# Main.net
KiCad netlist of a schematic drawn in Altium Designer
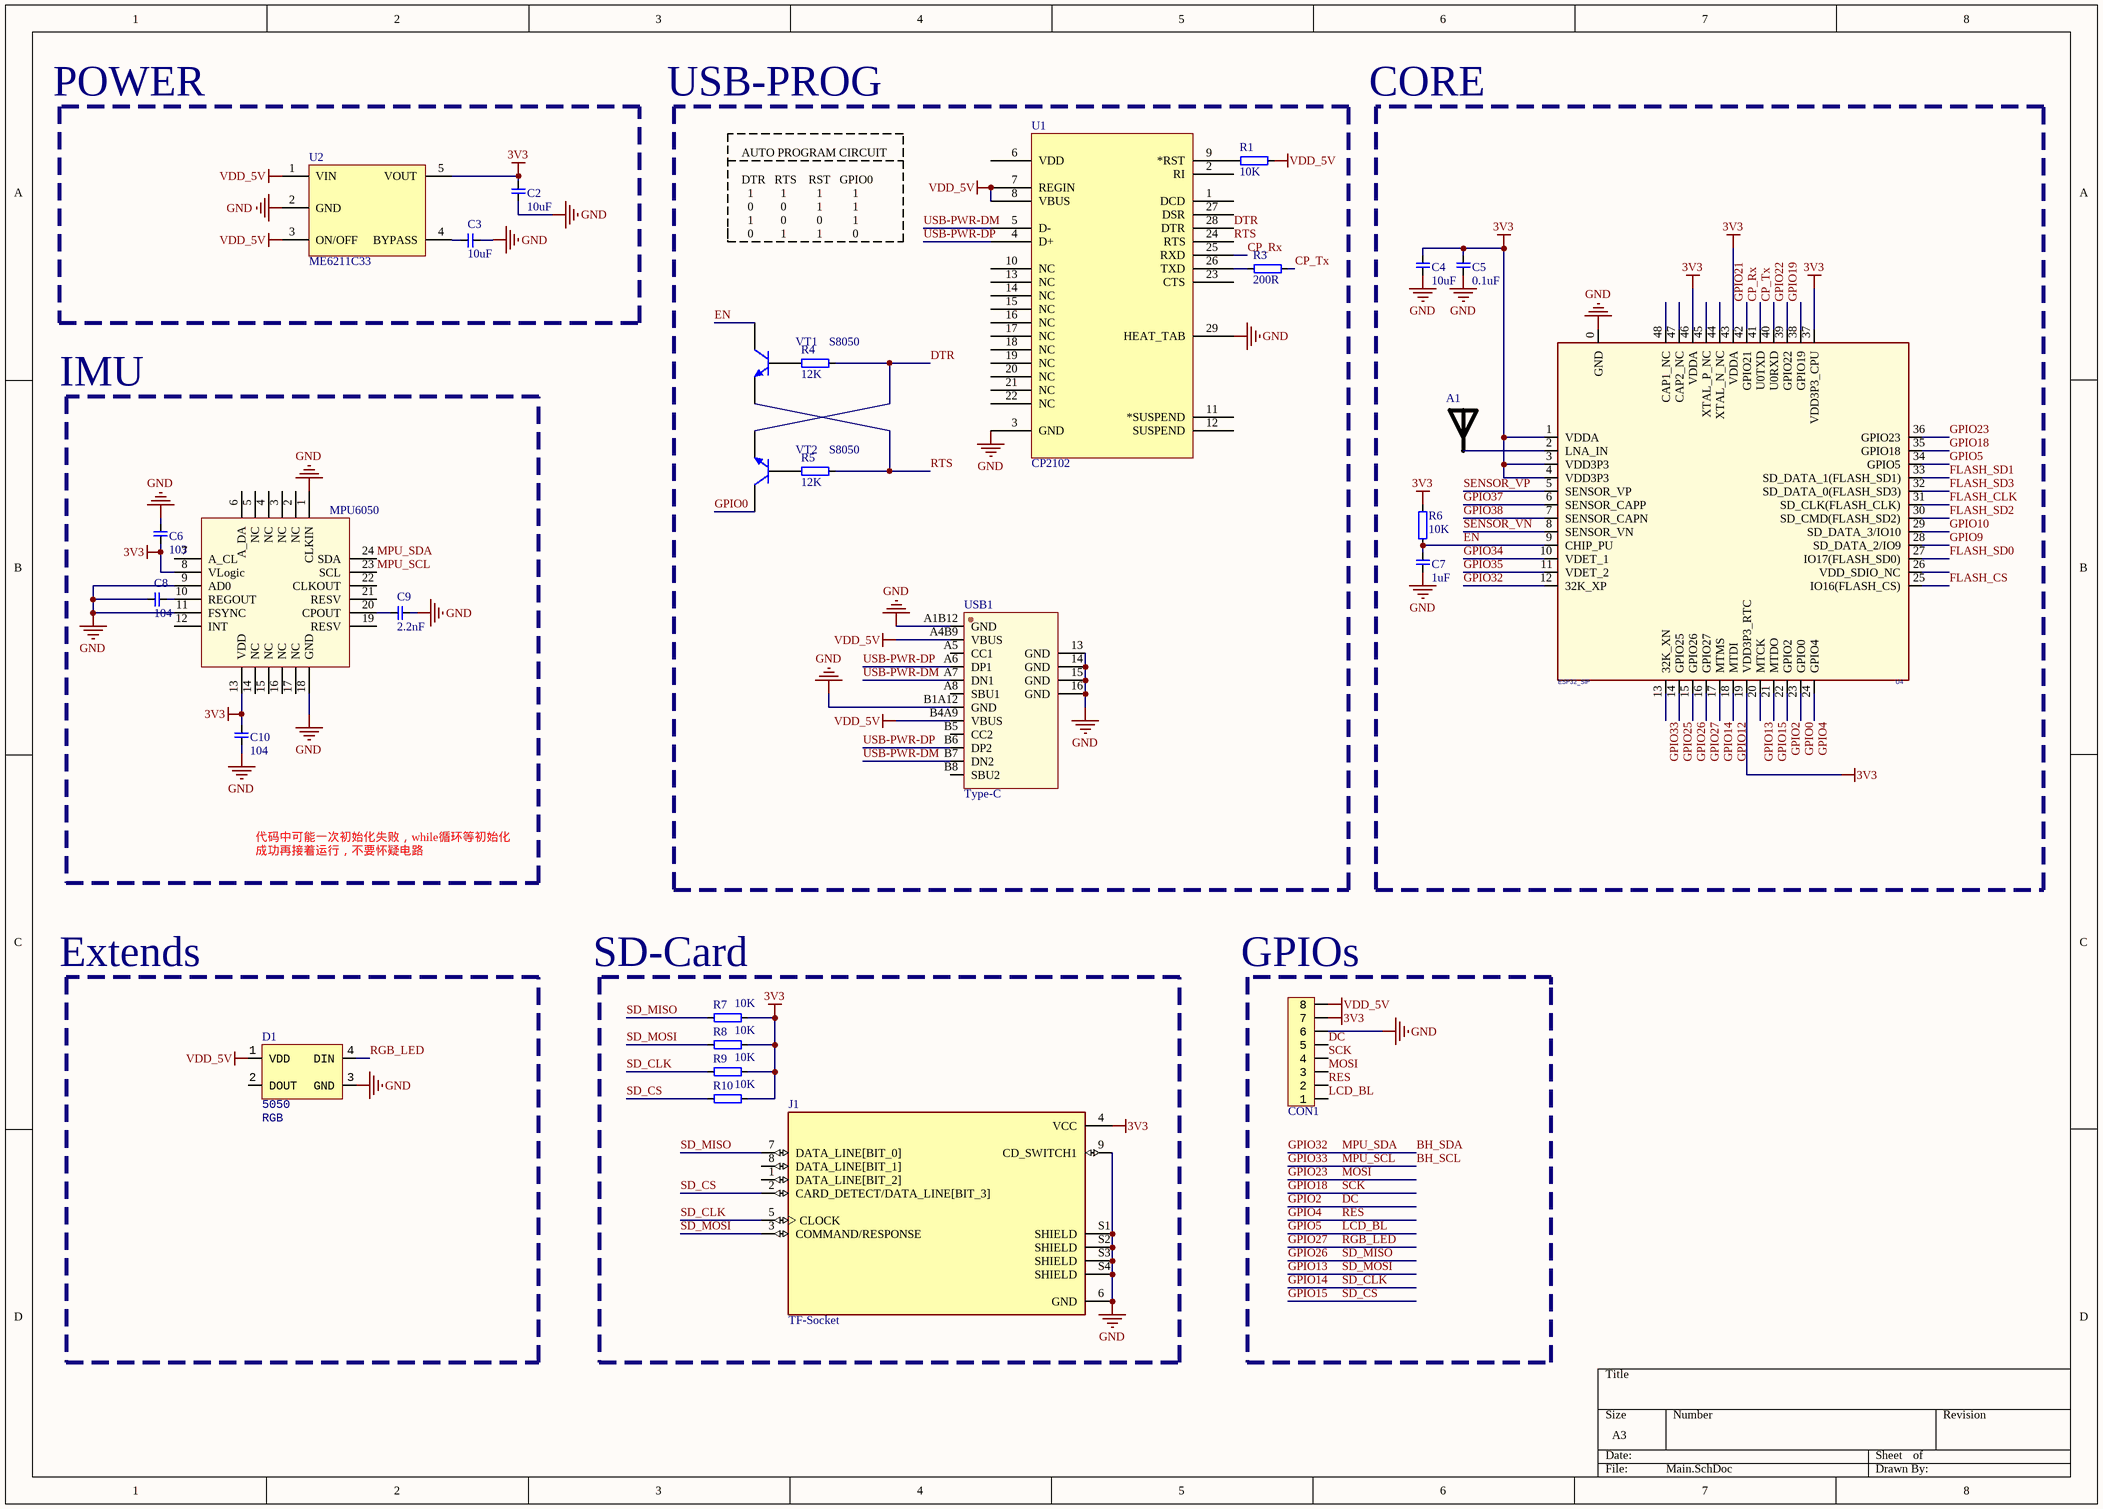
[diagram p0: Main.SchDoc]

(export (version "E")
  (design (tool "Eeschema 10.0.6"))
  (components
    (comp (ref "A1")
      (value "RAINSUN")
      (footprint "ANT-Rainsun-AN5120")
      (libsource (lib "MyPcbLib") (part "ANT-Rainsun-AP5120"))
    )
    (comp (ref "C2") (value "10uF") (footprint "CAP_0603") (libsource (lib "基本元件库") (part "cap")))
    (comp (ref "C3") (value "10uF") (footprint "CAP_0603") (libsource (lib "基本元件库") (part "cap")))
    (comp (ref "C4") (value "10uF") (footprint "CAP_0603") (libsource (lib "基本元件库") (part "cap")))
    (comp (ref "C5") (value "0.1uF") (footprint "CAP_0603") (libsource (lib "基本元件库") (part "cap")))
    (comp (ref "C6") (value "103") (footprint "CAP_0603") (libsource (lib "基本元件库") (part "cap")))
    (comp (ref "C7") (value "1uF") (footprint "CAP_0603") (libsource (lib "基本元件库") (part "cap")))
    (comp (ref "C8") (value "104") (footprint "CAP_0603") (libsource (lib "基本元件库") (part "cap")))
    (comp (ref "C9") (value "2.2nF") (footprint "CAP_0603") (libsource (lib "基本元件库") (part "cap")))
    (comp (ref "C10") (value "104") (footprint "CAP_0603") (libsource (lib "基本元件库") (part "cap")))
    (comp (ref "CON1")
      (value "FFC_0.5_8")
      (footprint "FFC_0.5_8")
      (description "FFC")
      (libsource (lib "KitSprout") (part "FFC_0.5_8"))
    )
    (comp (ref "D1")
      (value "RGB")
      (footprint "LED_5050_WS2812B")
      (description "LED")
      (fields (field (name "TYPE") "5050"))
      (libsource (lib "基本元件库") (part "RGB_4WIC"))
    )
    (comp (ref "J1")
      (value "TF-Socket")
      (footprint "TF-Card-Amphenol with TF - nohole")
      (description "9 _8 + 4_ Position Card Connector Secure Digital - microSDâ„¢ Surface Mount, Right Angle Gold")
      (fields (field (name "MP") "1140084168") (field (name "MF") "Amphenol Commercial Products"))
      (libsource (lib "IC") (part "TF-Socket"))
    )
    (comp (ref "R1") (value "10K") (footprint "RES_0603") (libsource (lib "基本元件库") (part "Res")))
    (comp (ref "R3") (value "200R") (footprint "RES_0603") (libsource (lib "基本元件库") (part "Res")))
    (comp (ref "R4") (value "12K") (footprint "RES_0603") (libsource (lib "基本元件库") (part "Res")))
    (comp (ref "R5") (value "12K") (footprint "RES_0603") (libsource (lib "基本元件库") (part "Res")))
    (comp (ref "R6") (value "10K") (footprint "RES_0603") (libsource (lib "基本元件库") (part "Res")))
    (comp (ref "R7") (value "10K") (footprint "RES_0603") (libsource (lib "基本元件库") (part "Res")))
    (comp (ref "R8") (value "10K") (footprint "RES_0603") (libsource (lib "基本元件库") (part "Res")))
    (comp (ref "R9") (value "10K") (footprint "RES_0603") (libsource (lib "基本元件库") (part "Res")))
    (comp (ref "R10") (value "10K") (footprint "RES_0603") (libsource (lib "基本元件库") (part "Res")))
    (comp (ref "U1")
      (value "CP2102")
      (footprint "QFN-28")
      (description "USB转TTL")
      (libsource (lib "mLib") (part "CP2102"))
    )
    (comp (ref "U2")
      (value "ME6211C33")
      (footprint "SOT23-5")
      (description "LDO")
      (libsource (lib "MyPcbLib") (part "LP2992"))
    )
    (comp (ref "U3")
      (value "MPU6050")
      (footprint "QFN-24")
      (description "六轴传感器")
      (libsource (lib "mLib") (part "MPU6050"))
    )
    (comp (ref "U4")
      (value "ESP32_SIP")
      (footprint "QFN-48_7X7")
      (libsource (lib "MyPcbLib") (part "ESP32-PICO"))
    )
    (comp (ref "USB1")
      (value "Type-C")
      (footprint "TypeC-304-16BCP")
      (libsource (lib "接插件库") (part "Type-C母口"))
    )
    (comp (ref "VT1")
      (value "S8050")
      (footprint "SMT_TRIODE_NPN")
      (description "Surface mount NPN transistor, package SOT-23")
      (libsource (lib "MyPcbLib") (part "SMT_TRIODE_NPN"))
    )
    (comp (ref "VT2")
      (value "S8050")
      (footprint "SMT_TRIODE_NPN")
      (description "Surface mount NPN transistor, package SOT-23")
      (libsource (lib "MyPcbLib") (part "SMT_TRIODE_NPN"))
    )
  )
  (nets
    (net (code "1") (name "/BH_SCL") (class "Default")
      (node (ref "U3") (pin "23") (pinfunction "SCL_23") (pintype "passive"))
      (node (ref "U4") (pin "13") (pinfunction "32K_XN_13") (pintype "passive"))
    )
    (net (code "2") (name "/BH_SDA") (class "Default")
      (node (ref "U3") (pin "24") (pinfunction "SDA_24") (pintype "passive"))
      (node (ref "U4") (pin "12") (pinfunction "32K_XP_12") (pintype "passive"))
    )
    (net (code "3") (name "/CP_Rx") (class "Default")
      (node (ref "U1") (pin "25") (pinfunction "RXD_25") (pintype "passive"))
      (node (ref "U4") (pin "41") (pinfunction "U0TXD_41") (pintype "power_in"))
    )
    (net (code "4") (name "/CP_Tx") (class "Default")
      (node (ref "R3") (pin "1") (pinfunction "1_1") (pintype "passive"))
      (node (ref "U4") (pin "40") (pinfunction "U0RXD_40") (pintype "power_in"))
    )
    (net (code "5") (name "/DC") (class "Default")
      (node (ref "CON1") (pin "5") (pinfunction "5_5") (pintype "passive"))
      (node (ref "U4") (pin "22") (pinfunction "GPIO2_22") (pintype "passive"))
    )
    (net (code "6") (name "/DTR") (class "Default")
      (node (ref "R4") (pin "1") (pinfunction "1_1") (pintype "passive"))
      (node (ref "U1") (pin "28") (pinfunction "DTR_28") (pintype "passive"))
      (node (ref "VT2") (pin "2") (pinfunction "E_2") (pintype "passive"))
    )
    (net (code "7") (name "/EN") (class "Default")
      (node (ref "C7") (pin "2") (pinfunction "2_2") (pintype "passive"))
      (node (ref "R6") (pin "1") (pinfunction "1_1") (pintype "passive"))
      (node (ref "U4") (pin "9") (pinfunction "CHIP_PU_9") (pintype "passive"))
      (node (ref "VT1") (pin "3") (pinfunction "C_3") (pintype "passive"))
    )
    (net (code "8") (name "/FLASH_CLK") (class "Default")
      (node (ref "U4") (pin "31") (pinfunction "SD_CLK(FLASH_CLK)_31") (pintype "passive"))
    )
    (net (code "9") (name "/FLASH_CS") (class "Default")
      (node (ref "U4") (pin "25") (pinfunction "IO16(FLASH_CS)_25") (pintype "passive"))
    )
    (net (code "10") (name "/FLASH_SD0") (class "Default")
      (node (ref "U4") (pin "27") (pinfunction "IO17(FLASH_SD0)_27") (pintype "passive"))
    )
    (net (code "11") (name "/FLASH_SD1") (class "Default")
      (node (ref "U4") (pin "33") (pinfunction "SD_DATA_1(FLASH_SD1)_33") (pintype "passive"))
    )
    (net (code "12") (name "/FLASH_SD2") (class "Default")
      (node (ref "U4") (pin "30") (pinfunction "SD_CMD(FLASH_SD2)_30") (pintype "passive"))
    )
    (net (code "13") (name "/FLASH_SD3") (class "Default")
      (node (ref "U4") (pin "32") (pinfunction "SD_DATA_0(FLASH_SD3)_32") (pintype "passive"))
    )
    (net (code "14") (name "/GPIO0") (class "Default")
      (node (ref "U4") (pin "23") (pinfunction "GPIO0_23") (pintype "passive"))
      (node (ref "VT2") (pin "3") (pinfunction "C_3") (pintype "passive"))
    )
    (net (code "15") (name "/GPIO4") (class "Default")
      (node (ref "CON1") (pin "2") (pinfunction "2_2") (pintype "passive"))
      (node (ref "U4") (pin "24") (pinfunction "GPIO4_24") (pintype "passive"))
    )
    (net (code "16") (name "/GPIO5") (class "Default")
      (node (ref "CON1") (pin "1") (pinfunction "1_1") (pintype "passive"))
      (node (ref "U4") (pin "34") (pinfunction "GPIO5_34") (pintype "passive"))
    )
    (net (code "17") (name "/GPIO9") (class "Default")
      (node (ref "U4") (pin "28") (pinfunction "SD_DATA_2/IO9_28") (pintype "passive"))
    )
    (net (code "18") (name "/GPIO10") (class "Default")
      (node (ref "U4") (pin "29") (pinfunction "SD_DATA_3/IO10_29") (pintype "passive"))
    )
    (net (code "19") (name "/GPIO12") (class "Default")
      (node (ref "U4") (pin "18") (pinfunction "MTDI_18") (pintype "passive"))
    )
    (net (code "20") (name "/GPIO13") (class "Default")
      (node (ref "J1") (pin "3") (pinfunction "COMMAND/RESPONSE_3") (pintype "bidirectional"))
      (node (ref "R8") (pin "2") (pinfunction "2_2") (pintype "passive"))
      (node (ref "U4") (pin "20") (pinfunction "MTCK_20") (pintype "passive"))
    )
    (net (code "21") (name "/GPIO14") (class "Default")
      (node (ref "J1") (pin "5") (pinfunction "CLOCK_5") (pintype "bidirectional"))
      (node (ref "R9") (pin "2") (pinfunction "2_2") (pintype "passive"))
      (node (ref "U4") (pin "17") (pinfunction "MTMS_17") (pintype "passive"))
    )
    (net (code "22") (name "/GPIO15") (class "Default")
      (node (ref "J1") (pin "2") (pinfunction "CARD_DETECT/DATA_LINE[BIT_3]_2") (pintype "bidirectional"))
      (node (ref "R10") (pin "2") (pinfunction "2_2") (pintype "passive"))
      (node (ref "U4") (pin "21") (pinfunction "MTDO_21") (pintype "passive"))
    )
    (net (code "23") (name "/GPIO18") (class "Default")
      (node (ref "CON1") (pin "4") (pinfunction "4_4") (pintype "passive"))
      (node (ref "U4") (pin "35") (pinfunction "GPIO18_35") (pintype "passive"))
    )
    (net (code "24") (name "/GPIO19") (class "Default")
      (node (ref "U4") (pin "38") (pinfunction "GPIO19_38") (pintype "passive"))
    )
    (net (code "25") (name "/GPIO21") (class "Default")
      (node (ref "U4") (pin "42") (pinfunction "GPIO21_42") (pintype "passive"))
    )
    (net (code "26") (name "/GPIO22") (class "Default")
      (node (ref "U4") (pin "39") (pinfunction "GPIO22_39") (pintype "passive"))
    )
    (net (code "27") (name "/GPIO23") (class "Default")
      (node (ref "CON1") (pin "3") (pinfunction "3_3") (pintype "passive"))
      (node (ref "U4") (pin "36") (pinfunction "GPIO23_36") (pintype "passive"))
    )
    (net (code "28") (name "/GPIO25") (class "Default")
      (node (ref "U4") (pin "14") (pinfunction "GPIO25_14") (pintype "passive"))
    )
    (net (code "29") (name "/GPIO26") (class "Default")
      (node (ref "J1") (pin "7") (pinfunction "DATA_LINE[BIT_0]_7") (pintype "bidirectional"))
      (node (ref "R7") (pin "2") (pinfunction "2_2") (pintype "passive"))
      (node (ref "U4") (pin "15") (pinfunction "GPIO26_15") (pintype "passive"))
    )
    (net (code "30") (name "/GPIO27") (class "Default")
      (node (ref "D1") (pin "4") (pinfunction "DIN_4") (pintype "passive"))
      (node (ref "U4") (pin "16") (pinfunction "GPIO27_16") (pintype "passive"))
    )
    (net (code "31") (name "/GPIO34") (class "Default")
      (node (ref "U4") (pin "10") (pinfunction "VDET_1_10") (pintype "passive"))
    )
    (net (code "32") (name "/GPIO35") (class "Default")
      (node (ref "U4") (pin "11") (pinfunction "VDET_2_11") (pintype "passive"))
    )
    (net (code "33") (name "/GPIO37") (class "Default")
      (node (ref "U4") (pin "6") (pinfunction "SENSOR_CAPP_6") (pintype "passive"))
    )
    (net (code "34") (name "/GPIO38") (class "Default")
      (node (ref "U4") (pin "7") (pinfunction "SENSOR_CAPN_7") (pintype "passive"))
    )
    (net (code "35") (name "/RTS") (class "Default")
      (node (ref "R5") (pin "1") (pinfunction "1_1") (pintype "passive"))
      (node (ref "U1") (pin "24") (pinfunction "RTS_24") (pintype "passive"))
      (node (ref "VT1") (pin "2") (pinfunction "E_2") (pintype "passive"))
    )
    (net (code "36") (name "/SENSOR_VN") (class "Default")
      (node (ref "U4") (pin "8") (pinfunction "SENSOR_VN_8") (pintype "passive"))
    )
    (net (code "37") (name "/SENSOR_VP") (class "Default")
      (node (ref "U4") (pin "5") (pinfunction "SENSOR_VP_5") (pintype "passive"))
    )
    (net (code "38") (name "/USB-PWR-DM") (class "Default")
      (node (ref "U1") (pin "5") (pinfunction "D-_5") (pintype "passive"))
      (node (ref "USB1") (pin "A7") (pinfunction "DN1_A7") (pintype "passive"))
      (node (ref "USB1") (pin "B7") (pinfunction "DN2_B7") (pintype "passive"))
    )
    (net (code "39") (name "/USB-PWR-DP") (class "Default")
      (node (ref "U1") (pin "4") (pinfunction "D+_4") (pintype "passive"))
      (node (ref "USB1") (pin "A6") (pinfunction "DP1_A6") (pintype "passive"))
      (node (ref "USB1") (pin "B6") (pinfunction "DP2_B6") (pintype "passive"))
    )
    (net (code "40") (name "3V3") (class "Default")
      (node (ref "C10") (pin "1") (pinfunction "1_1") (pintype "passive"))
      (node (ref "C2") (pin "2") (pinfunction "2_2") (pintype "passive"))
      (node (ref "C4") (pin "2") (pinfunction "2_2") (pintype "passive"))
      (node (ref "C5") (pin "2") (pinfunction "2_2") (pintype "passive"))
      (node (ref "C6") (pin "2") (pinfunction "2_2") (pintype "passive"))
      (node (ref "CON1") (pin "7") (pinfunction "7_7") (pintype "passive"))
      (node (ref "J1") (pin "4") (pinfunction "VCC_4") (pintype "power_in"))
      (node (ref "R10") (pin "1") (pinfunction "1_1") (pintype "passive"))
      (node (ref "R6") (pin "2") (pinfunction "2_2") (pintype "passive"))
      (node (ref "R7") (pin "1") (pinfunction "1_1") (pintype "passive"))
      (node (ref "R8") (pin "1") (pinfunction "1_1") (pintype "passive"))
      (node (ref "R9") (pin "1") (pinfunction "1_1") (pintype "passive"))
      (node (ref "U2") (pin "5") (pinfunction "VOUT_5") (pintype "passive"))
      (node (ref "U3") (pin "13") (pinfunction "VDD_13") (pintype "passive"))
      (node (ref "U3") (pin "8") (pinfunction "VLogic_8") (pintype "passive"))
      (node (ref "U4") (pin "1") (pinfunction "VDDA_1") (pintype "power_in"))
      (node (ref "U4") (pin "19") (pinfunction "VDD3P3_RTC_19") (pintype "power_in"))
      (node (ref "U4") (pin "3") (pinfunction "VDD3P3_3") (pintype "power_in"))
      (node (ref "U4") (pin "37") (pinfunction "VDD3P3_CPU_37") (pintype "power_in"))
      (node (ref "U4") (pin "4") (pinfunction "VDD3P3_4") (pintype "power_in"))
      (node (ref "U4") (pin "43") (pinfunction "VDDA_43") (pintype "power_in"))
      (node (ref "U4") (pin "46") (pinfunction "VDDA_46") (pintype "power_in"))
    )
    (net (code "41") (name "GND") (class "Default")
      (node (ref "C10") (pin "2") (pinfunction "2_2") (pintype "passive"))
      (node (ref "C2") (pin "1") (pinfunction "1_1") (pintype "passive"))
      (node (ref "C3") (pin "1") (pinfunction "1_1") (pintype "passive"))
      (node (ref "C4") (pin "1") (pinfunction "1_1") (pintype "passive"))
      (node (ref "C5") (pin "1") (pinfunction "1_1") (pintype "passive"))
      (node (ref "C6") (pin "1") (pinfunction "1_1") (pintype "passive"))
      (node (ref "C7") (pin "1") (pinfunction "1_1") (pintype "passive"))
      (node (ref "C8") (pin "2") (pinfunction "2_2") (pintype "passive"))
      (node (ref "C9") (pin "1") (pinfunction "1_1") (pintype "passive"))
      (node (ref "CON1") (pin "6") (pinfunction "6_6") (pintype "passive"))
      (node (ref "D1") (pin "3") (pinfunction "GND_3") (pintype "passive"))
      (node (ref "J1") (pin "6") (pinfunction "GND_6") (pintype "power_in"))
      (node (ref "J1") (pin "9") (pinfunction "CD_SWITCH1_9") (pintype "bidirectional"))
      (node (ref "J1") (pin "S1") (pinfunction "SHIELD_S1") (pintype "passive"))
      (node (ref "J1") (pin "S2") (pinfunction "SHIELD_S2") (pintype "passive"))
      (node (ref "J1") (pin "S3") (pinfunction "SHIELD_S3") (pintype "passive"))
      (node (ref "J1") (pin "S4") (pinfunction "SHIELD_S4") (pintype "passive"))
      (node (ref "U1") (pin "29") (pinfunction "HEAT_TAB_29") (pintype "passive"))
      (node (ref "U1") (pin "3") (pinfunction "GND_3") (pintype "passive"))
      (node (ref "U2") (pin "2") (pinfunction "GND_2") (pintype "passive"))
      (node (ref "U3") (pin "1") (pinfunction "CLKIN_1") (pintype "passive"))
      (node (ref "U3") (pin "11") (pinfunction "FSYNC_11") (pintype "passive"))
      (node (ref "U3") (pin "18") (pinfunction "GND_18") (pintype "passive"))
      (node (ref "U3") (pin "9") (pinfunction "AD0_9") (pintype "passive"))
      (node (ref "U4") (pin "0") (pinfunction "GND_0") (pintype "power_in"))
      (node (ref "USB1") (pin "13") (pinfunction "GND_13") (pintype "passive"))
      (node (ref "USB1") (pin "14") (pinfunction "GND_14") (pintype "passive"))
      (node (ref "USB1") (pin "15") (pinfunction "GND_15") (pintype "passive"))
      (node (ref "USB1") (pin "16") (pinfunction "GND_16") (pintype "passive"))
      (node (ref "USB1") (pin "A1B12") (pinfunction "GND_A1B12") (pintype "passive"))
      (node (ref "USB1") (pin "B1A12") (pinfunction "GND_B1A12") (pintype "passive"))
    )
    (net (code "42") (name "Net-(U1-*RST)") (class "Default")
      (node (ref "R1") (pin "2") (pinfunction "2_2") (pintype "passive"))
      (node (ref "U1") (pin "9") (pinfunction "*RST_9") (pintype "passive"))
    )
    (net (code "43") (name "Net-(U1-TXD)") (class "Default")
      (node (ref "R3") (pin "2") (pinfunction "2_2") (pintype "passive"))
      (node (ref "U1") (pin "26") (pinfunction "TXD_26") (pintype "passive"))
    )
    (net (code "44") (name "Net-(U2-BYPASS)") (class "Default")
      (node (ref "C3") (pin "2") (pinfunction "2_2") (pintype "passive"))
      (node (ref "U2") (pin "4") (pinfunction "BYPASS_4") (pintype "passive"))
    )
    (net (code "45") (name "Net-(U3-CPOUT)") (class "Default")
      (node (ref "C9") (pin "2") (pinfunction "2_2") (pintype "passive"))
      (node (ref "U3") (pin "20") (pinfunction "CPOUT_20") (pintype "passive"))
    )
    (net (code "46") (name "Net-(U3-REGOUT)") (class "Default")
      (node (ref "C8") (pin "1") (pinfunction "1_1") (pintype "passive"))
      (node (ref "U3") (pin "10") (pinfunction "REGOUT_10") (pintype "passive"))
    )
    (net (code "47") (name "Net-(U4-LNA_IN)") (class "Default")
      (node (ref "A1") (pin "1") (pinfunction "1_1") (pintype "passive"))
      (node (ref "U4") (pin "2") (pinfunction "LNA_IN_2") (pintype "passive"))
    )
    (net (code "48") (name "Net-(VT1-B)") (class "Default")
      (node (ref "R4") (pin "2") (pinfunction "2_2") (pintype "passive"))
      (node (ref "VT1") (pin "1") (pinfunction "B_1") (pintype "passive"))
    )
    (net (code "49") (name "Net-(VT2-B)") (class "Default")
      (node (ref "R5") (pin "2") (pinfunction "2_2") (pintype "passive"))
      (node (ref "VT2") (pin "1") (pinfunction "B_1") (pintype "passive"))
    )
    (net (code "50") (name "VDD_5V") (class "Default")
      (node (ref "CON1") (pin "8") (pinfunction "8_8") (pintype "passive"))
      (node (ref "D1") (pin "1") (pinfunction "VDD_1") (pintype "passive"))
      (node (ref "R1") (pin "1") (pinfunction "1_1") (pintype "passive"))
      (node (ref "U1") (pin "7") (pinfunction "REGIN_7") (pintype "passive"))
      (node (ref "U1") (pin "8") (pinfunction "VBUS_8") (pintype "passive"))
      (node (ref "U2") (pin "1") (pinfunction "VIN_1") (pintype "passive"))
      (node (ref "U2") (pin "3") (pinfunction "ON/OFF_3") (pintype "passive"))
      (node (ref "USB1") (pin "A4B9") (pinfunction "VBUS_A4B9") (pintype "passive"))
      (node (ref "USB1") (pin "B4A9") (pinfunction "VBUS_B4A9") (pintype "passive"))
    )
    (net (code "51") (name "unconnected-(D1-DOUT-Pad2)") (class "Default")
      (node (ref "D1") (pin "2") (pinfunction "DOUT_2") (pintype "passive"))
    )
    (net (code "52") (name "unconnected-(J1-DATA_LINE[BIT_1]-Pad8)") (class "Default")
      (node (ref "J1") (pin "8") (pinfunction "DATA_LINE[BIT_1]_8") (pintype "bidirectional"))
    )
    (net (code "53") (name "unconnected-(J1-DATA_LINE[BIT_2]-Pad1)") (class "Default")
      (node (ref "J1") (pin "1") (pinfunction "DATA_LINE[BIT_2]_1") (pintype "bidirectional"))
    )
    (net (code "54") (name "unconnected-(U1-*SUSPEND-Pad11)") (class "Default")
      (node (ref "U1") (pin "11") (pinfunction "*SUSPEND_11") (pintype "passive"))
    )
    (net (code "55") (name "unconnected-(U1-CTS-Pad23)") (class "Default")
      (node (ref "U1") (pin "23") (pinfunction "CTS_23") (pintype "passive"))
    )
    (net (code "56") (name "unconnected-(U1-DCD-Pad1)") (class "Default")
      (node (ref "U1") (pin "1") (pinfunction "DCD_1") (pintype "passive"))
    )
    (net (code "57") (name "unconnected-(U1-DSR-Pad27)") (class "Default")
      (node (ref "U1") (pin "27") (pinfunction "DSR_27") (pintype "passive"))
    )
    (net (code "58") (name "unconnected-(U1-NC-Pad10)") (class "Default")
      (node (ref "U1") (pin "10") (pinfunction "NC_10") (pintype "passive"))
    )
    (net (code "59") (name "unconnected-(U1-NC-Pad13)") (class "Default")
      (node (ref "U1") (pin "13") (pinfunction "NC_13") (pintype "passive"))
    )
    (net (code "60") (name "unconnected-(U1-NC-Pad14)") (class "Default")
      (node (ref "U1") (pin "14") (pinfunction "NC_14") (pintype "passive"))
    )
    (net (code "61") (name "unconnected-(U1-NC-Pad15)") (class "Default")
      (node (ref "U1") (pin "15") (pinfunction "NC_15") (pintype "passive"))
    )
    (net (code "62") (name "unconnected-(U1-NC-Pad16)") (class "Default")
      (node (ref "U1") (pin "16") (pinfunction "NC_16") (pintype "passive"))
    )
    (net (code "63") (name "unconnected-(U1-NC-Pad17)") (class "Default")
      (node (ref "U1") (pin "17") (pinfunction "NC_17") (pintype "passive"))
    )
    (net (code "64") (name "unconnected-(U1-NC-Pad18)") (class "Default")
      (node (ref "U1") (pin "18") (pinfunction "NC_18") (pintype "passive"))
    )
    (net (code "65") (name "unconnected-(U1-NC-Pad19)") (class "Default")
      (node (ref "U1") (pin "19") (pinfunction "NC_19") (pintype "passive"))
    )
    (net (code "66") (name "unconnected-(U1-NC-Pad20)") (class "Default")
      (node (ref "U1") (pin "20") (pinfunction "NC_20") (pintype "passive"))
    )
    (net (code "67") (name "unconnected-(U1-NC-Pad21)") (class "Default")
      (node (ref "U1") (pin "21") (pinfunction "NC_21") (pintype "passive"))
    )
    (net (code "68") (name "unconnected-(U1-NC-Pad22)") (class "Default")
      (node (ref "U1") (pin "22") (pinfunction "NC_22") (pintype "passive"))
    )
    (net (code "69") (name "unconnected-(U1-RI-Pad2)") (class "Default")
      (node (ref "U1") (pin "2") (pinfunction "RI_2") (pintype "passive"))
    )
    (net (code "70") (name "unconnected-(U1-SUSPEND-Pad12)") (class "Default")
      (node (ref "U1") (pin "12") (pinfunction "SUSPEND_12") (pintype "passive"))
    )
    (net (code "71") (name "unconnected-(U1-VDD-Pad6)") (class "Default")
      (node (ref "U1") (pin "6") (pinfunction "VDD_6") (pintype "passive"))
    )
    (net (code "72") (name "unconnected-(U3-A_CL-Pad7)") (class "Default")
      (node (ref "U3") (pin "7") (pinfunction "A_CL_7") (pintype "passive"))
    )
    (net (code "73") (name "unconnected-(U3-A_DA-Pad6)") (class "Default")
      (node (ref "U3") (pin "6") (pinfunction "A_DA_6") (pintype "passive"))
    )
    (net (code "74") (name "unconnected-(U3-CLKOUT-Pad22)") (class "Default")
      (node (ref "U3") (pin "22") (pinfunction "CLKOUT_22") (pintype "passive"))
    )
    (net (code "75") (name "unconnected-(U3-INT-Pad12)") (class "Default")
      (node (ref "U3") (pin "12") (pinfunction "INT_12") (pintype "passive"))
    )
    (net (code "76") (name "unconnected-(U3-NC-Pad2)") (class "Default")
      (node (ref "U3") (pin "2") (pinfunction "NC_2") (pintype "passive"))
    )
    (net (code "77") (name "unconnected-(U3-NC-Pad3)") (class "Default")
      (node (ref "U3") (pin "3") (pinfunction "NC_3") (pintype "passive"))
    )
    (net (code "78") (name "unconnected-(U3-NC-Pad4)") (class "Default")
      (node (ref "U3") (pin "4") (pinfunction "NC_4") (pintype "passive"))
    )
    (net (code "79") (name "unconnected-(U3-NC-Pad5)") (class "Default")
      (node (ref "U3") (pin "5") (pinfunction "NC_5") (pintype "passive"))
    )
    (net (code "80") (name "unconnected-(U3-NC-Pad14)") (class "Default")
      (node (ref "U3") (pin "14") (pinfunction "NC_14") (pintype "passive"))
    )
    (net (code "81") (name "unconnected-(U3-NC-Pad15)") (class "Default")
      (node (ref "U3") (pin "15") (pinfunction "NC_15") (pintype "passive"))
    )
    (net (code "82") (name "unconnected-(U3-NC-Pad16)") (class "Default")
      (node (ref "U3") (pin "16") (pinfunction "NC_16") (pintype "passive"))
    )
    (net (code "83") (name "unconnected-(U3-NC-Pad17)") (class "Default")
      (node (ref "U3") (pin "17") (pinfunction "NC_17") (pintype "passive"))
    )
    (net (code "84") (name "unconnected-(U3-RESV-Pad19)") (class "Default")
      (node (ref "U3") (pin "19") (pinfunction "RESV_19") (pintype "passive"))
    )
    (net (code "85") (name "unconnected-(U3-RESV-Pad21)") (class "Default")
      (node (ref "U3") (pin "21") (pinfunction "RESV_21") (pintype "passive"))
    )
    (net (code "86") (name "unconnected-(U4-CAP1_NC-Pad48)") (class "Default")
      (node (ref "U4") (pin "48") (pinfunction "CAP1_NC_48") (pintype "passive"))
    )
    (net (code "87") (name "unconnected-(U4-CAP2_NC-Pad47)") (class "Default")
      (node (ref "U4") (pin "47") (pinfunction "CAP2_NC_47") (pintype "passive"))
    )
    (net (code "88") (name "unconnected-(U4-VDD_SDIO_NC-Pad26)") (class "Default")
      (node (ref "U4") (pin "26") (pinfunction "VDD_SDIO_NC_26") (pintype "passive"))
    )
    (net (code "89") (name "unconnected-(U4-XTAL_N_NC-Pad44)") (class "Default")
      (node (ref "U4") (pin "44") (pinfunction "XTAL_N_NC_44") (pintype "passive"))
    )
    (net (code "90") (name "unconnected-(U4-XTAL_P_NC-Pad45)") (class "Default")
      (node (ref "U4") (pin "45") (pinfunction "XTAL_P_NC_45") (pintype "passive"))
    )
    (net (code "91") (name "unconnected-(USB1-CC1-PadA5)") (class "Default")
      (node (ref "USB1") (pin "A5") (pinfunction "CC1_A5") (pintype "passive"))
    )
    (net (code "92") (name "unconnected-(USB1-CC2-PadB5)") (class "Default")
      (node (ref "USB1") (pin "B5") (pinfunction "CC2_B5") (pintype "passive"))
    )
    (net (code "93") (name "unconnected-(USB1-SBU1-PadA8)") (class "Default")
      (node (ref "USB1") (pin "A8") (pinfunction "SBU1_A8") (pintype "passive"))
    )
    (net (code "94") (name "unconnected-(USB1-SBU2-PadB8)") (class "Default")
      (node (ref "USB1") (pin "B8") (pinfunction "SBU2_B8") (pintype "passive"))
    )
  )
)
